# filter.net
KiCad netlist of a schematic drawn in Altium Designer
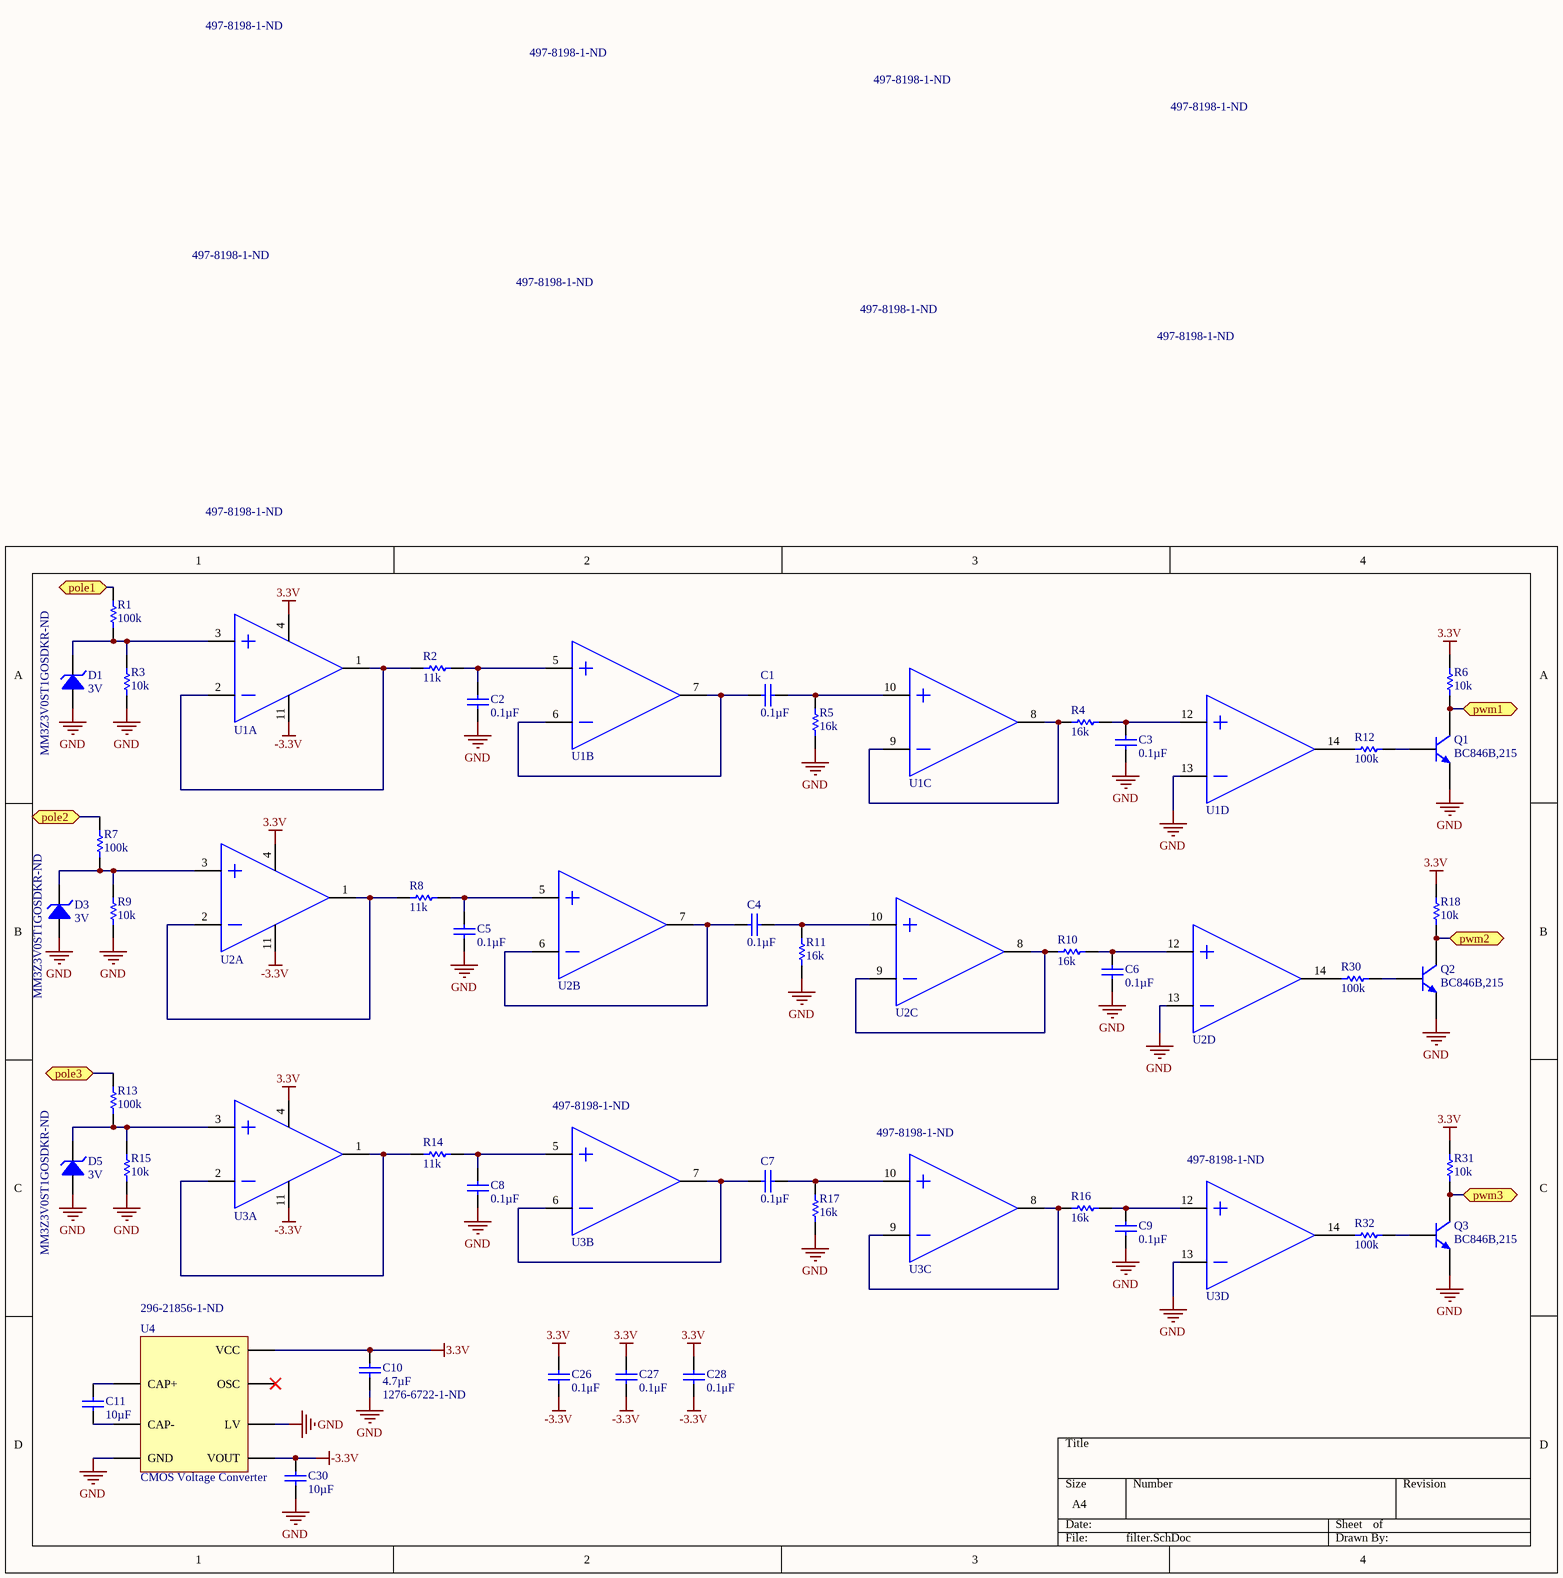
[diagram p0: filter.SchDoc]

(export (version "E")
  (design (tool "Eeschema 10.0.6"))
  (components
    (comp (ref "C1")
      (value "0.1uF, 50V, 10%, X7R, 1608")
      (footprint "CAPC1608N(0603\")")
      (description "CAP CER 0.1UF 50V 10% X7R 1608 (0603)")
      (fields
        (field (name "MANUFACTURER") "Samsung Electro-Mechanics America, Inc")
        (field (name "MANUFACTURER PART NUMBER") "CL10B104KB8SFNC")
        (field (name "CAPACITANCE") "0.1µF")
      )
      (libsource (lib "AUVic_Integrated_Library_Capacitors") (part "0.1uF, 50V, 10%, X7R, 1608"))
    )
    (comp (ref "C2")
      (value "0.1uF, 50V, 10%, X7R, 1608")
      (footprint "CAPC1608N(0603\")")
      (description "CAP CER 0.1UF 50V 10% X7R 1608 (0603)")
      (fields
        (field (name "MANUFACTURER") "Samsung Electro-Mechanics America, Inc")
        (field (name "MANUFACTURER PART NUMBER") "CL10B104KB8SFNC")
        (field (name "CAPACITANCE") "0.1µF")
      )
      (libsource (lib "AUVic_Integrated_Library_Capacitors") (part "0.1uF, 50V, 10%, X7R, 1608"))
    )
    (comp (ref "C3")
      (value "0.1uF, 50V, 10%, X7R, 1608")
      (footprint "CAPC1608N(0603\")")
      (description "CAP CER 0.1UF 50V 10% X7R 1608 (0603)")
      (fields
        (field (name "MANUFACTURER") "Samsung Electro-Mechanics America, Inc")
        (field (name "MANUFACTURER PART NUMBER") "CL10B104KB8SFNC")
        (field (name "CAPACITANCE") "0.1µF")
      )
      (libsource (lib "AUVic_Integrated_Library_Capacitors") (part "0.1uF, 50V, 10%, X7R, 1608"))
    )
    (comp (ref "C4")
      (value "0.1uF, 50V, 10%, X7R, 1608")
      (footprint "CAPC1608N(0603\")")
      (description "CAP CER 0.1UF 50V 10% X7R 1608 (0603)")
      (fields
        (field (name "MANUFACTURER") "Samsung Electro-Mechanics America, Inc")
        (field (name "MANUFACTURER PART NUMBER") "CL10B104KB8SFNC")
        (field (name "CAPACITANCE") "0.1µF")
      )
      (libsource (lib "AUVic_Integrated_Library_Capacitors") (part "0.1uF, 50V, 10%, X7R, 1608"))
    )
    (comp (ref "C5")
      (value "0.1uF, 50V, 10%, X7R, 1608")
      (footprint "CAPC1608N(0603\")")
      (description "CAP CER 0.1UF 50V 10% X7R 1608 (0603)")
      (fields
        (field (name "MANUFACTURER") "Samsung Electro-Mechanics America, Inc")
        (field (name "MANUFACTURER PART NUMBER") "CL10B104KB8SFNC")
        (field (name "CAPACITANCE") "0.1µF")
      )
      (libsource (lib "AUVic_Integrated_Library_Capacitors") (part "0.1uF, 50V, 10%, X7R, 1608"))
    )
    (comp (ref "C6")
      (value "0.1uF, 50V, 10%, X7R, 1608")
      (footprint "CAPC1608N(0603\")")
      (description "CAP CER 0.1UF 50V 10% X7R 1608 (0603)")
      (fields
        (field (name "MANUFACTURER") "Samsung Electro-Mechanics America, Inc")
        (field (name "MANUFACTURER PART NUMBER") "CL10B104KB8SFNC")
        (field (name "CAPACITANCE") "0.1µF")
      )
      (libsource (lib "AUVic_Integrated_Library_Capacitors") (part "0.1uF, 50V, 10%, X7R, 1608"))
    )
    (comp (ref "C7")
      (value "0.1uF, 50V, 10%, X7R, 1608")
      (footprint "CAPC1608N(0603\")")
      (description "CAP CER 0.1UF 50V 10% X7R 1608 (0603)")
      (fields
        (field (name "MANUFACTURER") "Samsung Electro-Mechanics America, Inc")
        (field (name "MANUFACTURER PART NUMBER") "CL10B104KB8SFNC")
        (field (name "CAPACITANCE") "0.1µF")
      )
      (libsource (lib "AUVic_Integrated_Library_Capacitors") (part "0.1uF, 50V, 10%, X7R, 1608"))
    )
    (comp (ref "C8")
      (value "0.1uF, 50V, 10%, X7R, 1608")
      (footprint "CAPC1608N(0603\")")
      (description "CAP CER 0.1UF 50V 10% X7R 1608 (0603)")
      (fields
        (field (name "MANUFACTURER") "Samsung Electro-Mechanics America, Inc")
        (field (name "MANUFACTURER PART NUMBER") "CL10B104KB8SFNC")
        (field (name "CAPACITANCE") "0.1µF")
      )
      (libsource (lib "AUVic_Integrated_Library_Capacitors") (part "0.1uF, 50V, 10%, X7R, 1608"))
    )
    (comp (ref "C9")
      (value "0.1uF, 50V, 10%, X7R, 1608")
      (footprint "CAPC1608N(0603\")")
      (description "CAP CER 0.1UF 50V 10% X7R 1608 (0603)")
      (fields
        (field (name "MANUFACTURER") "Samsung Electro-Mechanics America, Inc")
        (field (name "MANUFACTURER PART NUMBER") "CL10B104KB8SFNC")
        (field (name "CAPACITANCE") "0.1µF")
      )
      (libsource (lib "AUVic_Integrated_Library_Capacitors") (part "0.1uF, 50V, 10%, X7R, 1608"))
    )
    (comp (ref "C10")
      (value "4.7µF")
      (footprint "CAPC2012N(0805\")")
      (description "Capacitor, Ceramic, 35V, +/- 10%, 0805 SMD, X5R")
      (fields
        (field (name "SUPPLIER PART NUMBER 1") "1276-6722-1-ND")
        (field (name "PUBLISHER") "AUVic")
        (field (name "MADE BY") "Andy Bates")
      )
      (libsource (lib "AUVic_Integrated_Library_Capacitors") (part "4.7uF 35V 0805 SMD, Ceramic"))
    )
    (comp (ref "C11")
      (value "10µF")
      (footprint "CAPC3216N(1206\")")
      (description "Capacitor, Ceramic, 50V, +/- 10%, 1206 SMD, X5R")
      (fields (field (name "PUBLISHER") "AUVic"))
      (libsource (lib "AUVic_Integrated_Library_Capacitors") (part "10uF 50V 1206 SMD, Ceramic"))
    )
    (comp (ref "C26")
      (value "0.1μF")
      (footprint "CAPC1608N(0603\")")
      (description "Capacitor, Ceramic, 100V, +/- 10%, 0603 SMD, X7R")
      (fields
        (field (name "MFG") "TDK")
        (field (name "PUBLISHER") "AUVic")
        (field (name "CREATED BY") "Ashwin Sira")
      )
      (libsource (lib "AUVic_Integrated_Library_Capacitors") (part "0.1uF 100V 0603 SMD, Ceramic"))
    )
    (comp (ref "C27")
      (value "0.1μF")
      (footprint "CAPC1608N(0603\")")
      (description "Capacitor, Ceramic, 100V, +/- 10%, 0603 SMD, X7R")
      (fields
        (field (name "MFG") "TDK")
        (field (name "PUBLISHER") "AUVic")
        (field (name "CREATED BY") "Ashwin Sira")
      )
      (libsource (lib "AUVic_Integrated_Library_Capacitors") (part "0.1uF 100V 0603 SMD, Ceramic"))
    )
    (comp (ref "C28")
      (value "0.1μF")
      (footprint "CAPC1608N(0603\")")
      (description "Capacitor, Ceramic, 100V, +/- 10%, 0603 SMD, X7R")
      (fields
        (field (name "MFG") "TDK")
        (field (name "PUBLISHER") "AUVic")
        (field (name "CREATED BY") "Ashwin Sira")
      )
      (libsource (lib "AUVic_Integrated_Library_Capacitors") (part "0.1uF 100V 0603 SMD, Ceramic"))
    )
    (comp (ref "C30")
      (value "10µF")
      (footprint "CAPC2012N(0805\")")
      (description "Capacitor, Ceramic, 10V, +/- 10%, 0805 SMD, X5R")
      (fields (field (name "PUBLISHER") "AUVic") (field (name "MADE BY") "Andy Bates"))
      (libsource (lib "AUVic_Integrated_Library_Capacitors") (part "10uF 10V 0805 SMD, Ceramic"))
    )
    (comp (ref "D1")
      (value "ZENER MM3Z3V0ST1G")
      (footprint "SC-90")
      (description "DIODE ZENER 11V 200MW ±5% SOD323")
      (fields
        (field (name "TOLERANCE") "±5%")
        (field (name "VOLTAGE - ZENER (NOM) (VZ)") "3V")
        (field (name "SUPPLIER PART NUMBER 1") "MM3Z3V0ST1GOSDKR-ND")
      )
      (libsource (lib "AUVic_Integrated_Library_Diodes") (part "ZENER MM3Z3V0ST1G"))
    )
    (comp (ref "D3")
      (value "ZENER MM3Z3V0ST1G")
      (footprint "SC-90")
      (description "DIODE ZENER 11V 200MW ±5% SOD323")
      (fields
        (field (name "TOLERANCE") "±5%")
        (field (name "VOLTAGE - ZENER (NOM) (VZ)") "3V")
        (field (name "SUPPLIER PART NUMBER 1") "MM3Z3V0ST1GOSDKR-ND")
      )
      (libsource (lib "AUVic_Integrated_Library_Diodes") (part "ZENER MM3Z3V0ST1G"))
    )
    (comp (ref "D5")
      (value "ZENER MM3Z3V0ST1G")
      (footprint "SC-90")
      (description "DIODE ZENER 11V 200MW ±5% SOD323")
      (fields
        (field (name "TOLERANCE") "±5%")
        (field (name "VOLTAGE - ZENER (NOM) (VZ)") "3V")
        (field (name "SUPPLIER PART NUMBER 1") "MM3Z3V0ST1GOSDKR-ND")
      )
      (libsource (lib "AUVic_Integrated_Library_Diodes") (part "ZENER MM3Z3V0ST1G"))
    )
    (comp (ref "Q1")
      (value "BC846B,215")
      (footprint "SOT-23")
      (description "NPN 65V 100mA 250mW")
      (fields (field (name "PUBLISHER") "Andy Bates"))
      (libsource (lib "AUVic_Integrated_Library_Transistors") (part "BC846B,215"))
    )
    (comp (ref "Q2")
      (value "BC846B,215")
      (footprint "SOT-23")
      (description "NPN 65V 100mA 250mW")
      (fields (field (name "PUBLISHER") "Andy Bates"))
      (libsource (lib "AUVic_Integrated_Library_Transistors") (part "BC846B,215"))
    )
    (comp (ref "Q3")
      (value "BC846B,215")
      (footprint "SOT-23")
      (description "NPN 65V 100mA 250mW")
      (fields (field (name "PUBLISHER") "Andy Bates"))
      (libsource (lib "AUVic_Integrated_Library_Transistors") (part "BC846B,215"))
    )
    (comp (ref "R1")
      (value "100k")
      (footprint "RESC1608N(0603\")")
      (description "100kR, 1%, 1/10W, 0603 SMD")
      (fields (field (name "MADE BY") "Andy Bates"))
      (libsource (lib "AUVic_Integrated_Library_Resistors") (part "100kR, 1%, 1/10W, 0603 SMD"))
    )
    (comp (ref "R2")
      (value "11k")
      (footprint "RESC1608N(0603\")")
      (description "11kR, 1%, 1/10W, 0603 SMD")
      (fields (field (name "MADE BY") "Ashwin Sira"))
      (libsource (lib "AUVic_Integrated_Library_Resistors") (part "11kR, 1%, 1/10W, 0603 SMD"))
    )
    (comp (ref "R3")
      (value "10k")
      (footprint "RESC1608N(0603\")")
      (description "10kR, 1%, 1/10W, 0603 SMD")
      (fields (field (name "MADE BY") "Ashwin Sira"))
      (libsource (lib "AUVic_Integrated_Library_Resistors") (part "10kR, 1%, 1/10W, 0603 SMD"))
    )
    (comp (ref "R4")
      (value "16k")
      (footprint "RESC1608N(0603\")")
      (description "16kR, 1%, 1/10W, 0603 SMD")
      (fields (field (name "MADE BY") "Ashwin Sira"))
      (libsource (lib "AUVic_Integrated_Library_Resistors") (part "16kR, 1%, 1/10W, 0603 SMD"))
    )
    (comp (ref "R5")
      (value "16k")
      (footprint "RESC1608N(0603\")")
      (description "16kR, 1%, 1/10W, 0603 SMD")
      (fields (field (name "MADE BY") "Ashwin Sira"))
      (libsource (lib "AUVic_Integrated_Library_Resistors") (part "16kR, 1%, 1/10W, 0603 SMD"))
    )
    (comp (ref "R6")
      (value "10k")
      (footprint "RESC1608N(0603\")")
      (description "10kR, 1%, 1/10W, 0603 SMD")
      (fields (field (name "MADE BY") "Ashwin Sira"))
      (libsource (lib "AUVic_Integrated_Library_Resistors") (part "10kR, 1%, 1/10W, 0603 SMD"))
    )
    (comp (ref "R7")
      (value "100k")
      (footprint "RESC1608N(0603\")")
      (description "100kR, 1%, 1/10W, 0603 SMD")
      (fields (field (name "MADE BY") "Andy Bates"))
      (libsource (lib "AUVic_Integrated_Library_Resistors") (part "100kR, 1%, 1/10W, 0603 SMD"))
    )
    (comp (ref "R8")
      (value "11k")
      (footprint "RESC1608N(0603\")")
      (description "11kR, 1%, 1/10W, 0603 SMD")
      (fields (field (name "MADE BY") "Ashwin Sira"))
      (libsource (lib "AUVic_Integrated_Library_Resistors") (part "11kR, 1%, 1/10W, 0603 SMD"))
    )
    (comp (ref "R9")
      (value "10k")
      (footprint "RESC1608N(0603\")")
      (description "10kR, 1%, 1/10W, 0603 SMD")
      (fields (field (name "MADE BY") "Ashwin Sira"))
      (libsource (lib "AUVic_Integrated_Library_Resistors") (part "10kR, 1%, 1/10W, 0603 SMD"))
    )
    (comp (ref "R10")
      (value "16k")
      (footprint "RESC1608N(0603\")")
      (description "16kR, 1%, 1/10W, 0603 SMD")
      (fields (field (name "MADE BY") "Ashwin Sira"))
      (libsource (lib "AUVic_Integrated_Library_Resistors") (part "16kR, 1%, 1/10W, 0603 SMD"))
    )
    (comp (ref "R11")
      (value "16k")
      (footprint "RESC1608N(0603\")")
      (description "16kR, 1%, 1/10W, 0603 SMD")
      (fields (field (name "MADE BY") "Ashwin Sira"))
      (libsource (lib "AUVic_Integrated_Library_Resistors") (part "16kR, 1%, 1/10W, 0603 SMD"))
    )
    (comp (ref "R12")
      (value "100k")
      (footprint "RESC1608N(0603\")")
      (description "100kR, 1%, 1/10W, 0603 SMD")
      (fields (field (name "MADE BY") "Andy Bates"))
      (libsource (lib "AUVic_Integrated_Library_Resistors") (part "100kR, 1%, 1/10W, 0603 SMD"))
    )
    (comp (ref "R13")
      (value "100k")
      (footprint "RESC1608N(0603\")")
      (description "100kR, 1%, 1/10W, 0603 SMD")
      (fields (field (name "MADE BY") "Andy Bates"))
      (libsource (lib "AUVic_Integrated_Library_Resistors") (part "100kR, 1%, 1/10W, 0603 SMD"))
    )
    (comp (ref "R14")
      (value "11k")
      (footprint "RESC1608N(0603\")")
      (description "11kR, 1%, 1/10W, 0603 SMD")
      (fields (field (name "MADE BY") "Ashwin Sira"))
      (libsource (lib "AUVic_Integrated_Library_Resistors") (part "11kR, 1%, 1/10W, 0603 SMD"))
    )
    (comp (ref "R15")
      (value "10k")
      (footprint "RESC1608N(0603\")")
      (description "10kR, 1%, 1/10W, 0603 SMD")
      (fields (field (name "MADE BY") "Ashwin Sira"))
      (libsource (lib "AUVic_Integrated_Library_Resistors") (part "10kR, 1%, 1/10W, 0603 SMD"))
    )
    (comp (ref "R16")
      (value "16k")
      (footprint "RESC1608N(0603\")")
      (description "16kR, 1%, 1/10W, 0603 SMD")
      (fields (field (name "MADE BY") "Ashwin Sira"))
      (libsource (lib "AUVic_Integrated_Library_Resistors") (part "16kR, 1%, 1/10W, 0603 SMD"))
    )
    (comp (ref "R17")
      (value "16k")
      (footprint "RESC1608N(0603\")")
      (description "16kR, 1%, 1/10W, 0603 SMD")
      (fields (field (name "MADE BY") "Ashwin Sira"))
      (libsource (lib "AUVic_Integrated_Library_Resistors") (part "16kR, 1%, 1/10W, 0603 SMD"))
    )
    (comp (ref "R18")
      (value "10k")
      (footprint "RESC1608N(0603\")")
      (description "10kR, 1%, 1/10W, 0603 SMD")
      (fields (field (name "MADE BY") "Ashwin Sira"))
      (libsource (lib "AUVic_Integrated_Library_Resistors") (part "10kR, 1%, 1/10W, 0603 SMD"))
    )
    (comp (ref "R30")
      (value "100k")
      (footprint "RESC1608N(0603\")")
      (description "100kR, 1%, 1/10W, 0603 SMD")
      (fields (field (name "MADE BY") "Andy Bates"))
      (libsource (lib "AUVic_Integrated_Library_Resistors") (part "100kR, 1%, 1/10W, 0603 SMD"))
    )
    (comp (ref "R31")
      (value "10k")
      (footprint "RESC1608N(0603\")")
      (description "10kR, 1%, 1/10W, 0603 SMD")
      (fields (field (name "MADE BY") "Ashwin Sira"))
      (libsource (lib "AUVic_Integrated_Library_Resistors") (part "10kR, 1%, 1/10W, 0603 SMD"))
    )
    (comp (ref "R32")
      (value "100k")
      (footprint "RESC1608N(0603\")")
      (description "100kR, 1%, 1/10W, 0603 SMD")
      (fields (field (name "MADE BY") "Andy Bates"))
      (libsource (lib "AUVic_Integrated_Library_Resistors") (part "100kR, 1%, 1/10W, 0603 SMD"))
    )
    (comp (ref "U1")
      (value "Quad Op Amp TSV324")
      (footprint "SOP-14")
      (description "TSV324")
      (fields
        (field (name "SUPPLIER PART NUMBER 1") "497-8198-1-ND")
        (field (name "PUBLISHER") "Altium Limited")
        (field (name "CREATED BY") "Jordan")
      )
      (libsource (lib "AUVic_Integrated_Library_Op_amps") (part "Quad Op Amp TSV324"))
    )
    (comp (ref "U2")
      (value "Quad Op Amp TSV324")
      (footprint "SOP-14")
      (description "TSV324")
      (fields
        (field (name "SUPPLIER PART NUMBER 1") "497-8198-1-ND")
        (field (name "PUBLISHER") "Altium Limited")
        (field (name "CREATED BY") "Jordan")
      )
      (libsource (lib "AUVic_Integrated_Library_Op_amps") (part "Quad Op Amp TSV324"))
    )
    (comp (ref "U3")
      (value "Quad Op Amp TSV324")
      (footprint "SOP-14")
      (description "TSV324")
      (fields
        (field (name "SUPPLIER PART NUMBER 1") "497-8198-1-ND")
        (field (name "PUBLISHER") "Altium Limited")
        (field (name "CREATED BY") "Jordan")
      )
      (libsource (lib "AUVic_Integrated_Library_Op_amps") (part "Quad Op Amp TSV324"))
    )
    (comp (ref "U4")
      (value "CMOS Voltage Converter")
      (footprint "8-SOIC")
      (fields
        (field (name "MANUFACTURER PART NO.") "TL7660")
        (field (name "SUPPLIER PART NUMBER 1") "296-21856-1-ND")
        (field (name "PUBLISHER") "Altium Limited")
        (field (name "CREATED BY") "Jordan")
      )
      (libsource (lib "AUVic_Integrated_Library_Regulators") (part "TL7660"))
    )
  )
  (nets
    (net (code "1") (name "-3.3V") (class "Default")
      (node (ref "C26") (pin "1") (pinfunction "Anode_1") (pintype "passive"))
      (node (ref "C27") (pin "1") (pinfunction "Anode_1") (pintype "passive"))
      (node (ref "C28") (pin "1") (pinfunction "Anode_1") (pintype "passive"))
      (node (ref "C30") (pin "2") (pinfunction "Cathode_2") (pintype "passive"))
      (node (ref "U1") (pin "11") (pinfunction "Vcc-_11") (pintype "passive"))
      (node (ref "U2") (pin "11") (pinfunction "Vcc-_11") (pintype "passive"))
      (node (ref "U3") (pin "11") (pinfunction "Vcc-_11") (pintype "passive"))
      (node (ref "U4") (pin "5") (pinfunction "VOUT_5") (pintype "passive"))
    )
    (net (code "2") (name "/pole1") (class "Default")
      (node (ref "R1") (pin "2") (pinfunction "2_2") (pintype "passive"))
    )
    (net (code "3") (name "/pole2") (class "Default")
      (node (ref "R7") (pin "2") (pinfunction "2_2") (pintype "passive"))
    )
    (net (code "4") (name "/pole3") (class "Default")
      (node (ref "R13") (pin "2") (pinfunction "2_2") (pintype "passive"))
    )
    (net (code "5") (name "/pwm1") (class "Default")
      (node (ref "Q1") (pin "3") (pinfunction "C_3") (pintype "passive"))
      (node (ref "R6") (pin "1") (pinfunction "1_1") (pintype "passive"))
    )
    (net (code "6") (name "/pwm2") (class "Default")
      (node (ref "Q2") (pin "3") (pinfunction "C_3") (pintype "passive"))
      (node (ref "R18") (pin "1") (pinfunction "1_1") (pintype "passive"))
    )
    (net (code "7") (name "/pwm3") (class "Default")
      (node (ref "Q3") (pin "3") (pinfunction "C_3") (pintype "passive"))
      (node (ref "R31") (pin "1") (pinfunction "1_1") (pintype "passive"))
    )
    (net (code "8") (name "3.3V") (class "Default")
      (node (ref "C10") (pin "2") (pinfunction "Cathode_2") (pintype "passive"))
      (node (ref "C26") (pin "2") (pinfunction "Cathode_2") (pintype "passive"))
      (node (ref "C27") (pin "2") (pinfunction "Cathode_2") (pintype "passive"))
      (node (ref "C28") (pin "2") (pinfunction "Cathode_2") (pintype "passive"))
      (node (ref "R18") (pin "2") (pinfunction "2_2") (pintype "passive"))
      (node (ref "R31") (pin "2") (pinfunction "2_2") (pintype "passive"))
      (node (ref "R6") (pin "2") (pinfunction "2_2") (pintype "passive"))
      (node (ref "U1") (pin "4") (pinfunction "Vcc+_4") (pintype "passive"))
      (node (ref "U2") (pin "4") (pinfunction "Vcc+_4") (pintype "passive"))
      (node (ref "U3") (pin "4") (pinfunction "Vcc+_4") (pintype "passive"))
      (node (ref "U4") (pin "8") (pinfunction "VCC_8") (pintype "passive"))
    )
    (net (code "9") (name "GND") (class "Default")
      (node (ref "C10") (pin "1") (pinfunction "Anode_1") (pintype "passive"))
      (node (ref "C2") (pin "1") (pinfunction "Anode_1") (pintype "passive"))
      (node (ref "C3") (pin "1") (pinfunction "Anode_1") (pintype "passive"))
      (node (ref "C30") (pin "1") (pinfunction "Anode_1") (pintype "passive"))
      (node (ref "C5") (pin "1") (pinfunction "Anode_1") (pintype "passive"))
      (node (ref "C6") (pin "1") (pinfunction "Anode_1") (pintype "passive"))
      (node (ref "C8") (pin "1") (pinfunction "Anode_1") (pintype "passive"))
      (node (ref "C9") (pin "1") (pinfunction "Anode_1") (pintype "passive"))
      (node (ref "D1") (pin "A") (pinfunction "Anode_A") (pintype "passive"))
      (node (ref "D3") (pin "A") (pinfunction "Anode_A") (pintype "passive"))
      (node (ref "D5") (pin "A") (pinfunction "Anode_A") (pintype "passive"))
      (node (ref "Q1") (pin "2") (pinfunction "E_2") (pintype "passive"))
      (node (ref "Q2") (pin "2") (pinfunction "E_2") (pintype "passive"))
      (node (ref "Q3") (pin "2") (pinfunction "E_2") (pintype "passive"))
      (node (ref "R11") (pin "1") (pinfunction "1_1") (pintype "passive"))
      (node (ref "R15") (pin "1") (pinfunction "1_1") (pintype "passive"))
      (node (ref "R17") (pin "1") (pinfunction "1_1") (pintype "passive"))
      (node (ref "R3") (pin "1") (pinfunction "1_1") (pintype "passive"))
      (node (ref "R5") (pin "1") (pinfunction "1_1") (pintype "passive"))
      (node (ref "R9") (pin "1") (pinfunction "1_1") (pintype "passive"))
      (node (ref "U1") (pin "13") (pinfunction "Inverting_Input_3_13") (pintype "passive"))
      (node (ref "U2") (pin "13") (pinfunction "Inverting_Input_3_13") (pintype "passive"))
      (node (ref "U3") (pin "13") (pinfunction "Inverting_Input_3_13") (pintype "passive"))
      (node (ref "U4") (pin "3") (pinfunction "GND_3") (pintype "passive"))
      (node (ref "U4") (pin "6") (pinfunction "LV_6") (pintype "passive"))
    )
    (net (code "10") (name "Net-(C1-Anode)") (class "Default")
      (node (ref "C1") (pin "1") (pinfunction "Anode_1") (pintype "passive"))
      (node (ref "U1") (pin "6") (pinfunction "Inverting_Input_2_6") (pintype "passive"))
      (node (ref "U1") (pin "7") (pinfunction "Output_2_7") (pintype "passive"))
    )
    (net (code "11") (name "Net-(C1-Cathode)") (class "Default")
      (node (ref "C1") (pin "2") (pinfunction "Cathode_2") (pintype "passive"))
      (node (ref "R5") (pin "2") (pinfunction "2_2") (pintype "passive"))
      (node (ref "U1") (pin "10") (pinfunction "Non-Inverting_Input_3_10") (pintype "passive"))
    )
    (net (code "12") (name "Net-(C2-Cathode)") (class "Default")
      (node (ref "C2") (pin "2") (pinfunction "Cathode_2") (pintype "passive"))
      (node (ref "R2") (pin "2") (pinfunction "2_2") (pintype "passive"))
      (node (ref "U1") (pin "5") (pinfunction "Non-Inverting_Input_2_5") (pintype "passive"))
    )
    (net (code "13") (name "Net-(C3-Cathode)") (class "Default")
      (node (ref "C3") (pin "2") (pinfunction "Cathode_2") (pintype "passive"))
      (node (ref "R4") (pin "1") (pinfunction "1_1") (pintype "passive"))
      (node (ref "U1") (pin "12") (pinfunction "Non-Inverting_Input_4_12") (pintype "passive"))
    )
    (net (code "14") (name "Net-(C4-Anode)") (class "Default")
      (node (ref "C4") (pin "1") (pinfunction "Anode_1") (pintype "passive"))
      (node (ref "U2") (pin "6") (pinfunction "Inverting_Input_2_6") (pintype "passive"))
      (node (ref "U2") (pin "7") (pinfunction "Output_2_7") (pintype "passive"))
    )
    (net (code "15") (name "Net-(C4-Cathode)") (class "Default")
      (node (ref "C4") (pin "2") (pinfunction "Cathode_2") (pintype "passive"))
      (node (ref "R11") (pin "2") (pinfunction "2_2") (pintype "passive"))
      (node (ref "U2") (pin "10") (pinfunction "Non-Inverting_Input_3_10") (pintype "passive"))
    )
    (net (code "16") (name "Net-(C5-Cathode)") (class "Default")
      (node (ref "C5") (pin "2") (pinfunction "Cathode_2") (pintype "passive"))
      (node (ref "R8") (pin "2") (pinfunction "2_2") (pintype "passive"))
      (node (ref "U2") (pin "5") (pinfunction "Non-Inverting_Input_2_5") (pintype "passive"))
    )
    (net (code "17") (name "Net-(C6-Cathode)") (class "Default")
      (node (ref "C6") (pin "2") (pinfunction "Cathode_2") (pintype "passive"))
      (node (ref "R10") (pin "1") (pinfunction "1_1") (pintype "passive"))
      (node (ref "U2") (pin "12") (pinfunction "Non-Inverting_Input_4_12") (pintype "passive"))
    )
    (net (code "18") (name "Net-(C7-Anode)") (class "Default")
      (node (ref "C7") (pin "1") (pinfunction "Anode_1") (pintype "passive"))
      (node (ref "U3") (pin "6") (pinfunction "Inverting_Input_2_6") (pintype "passive"))
      (node (ref "U3") (pin "7") (pinfunction "Output_2_7") (pintype "passive"))
    )
    (net (code "19") (name "Net-(C7-Cathode)") (class "Default")
      (node (ref "C7") (pin "2") (pinfunction "Cathode_2") (pintype "passive"))
      (node (ref "R17") (pin "2") (pinfunction "2_2") (pintype "passive"))
      (node (ref "U3") (pin "10") (pinfunction "Non-Inverting_Input_3_10") (pintype "passive"))
    )
    (net (code "20") (name "Net-(C8-Cathode)") (class "Default")
      (node (ref "C8") (pin "2") (pinfunction "Cathode_2") (pintype "passive"))
      (node (ref "R14") (pin "2") (pinfunction "2_2") (pintype "passive"))
      (node (ref "U3") (pin "5") (pinfunction "Non-Inverting_Input_2_5") (pintype "passive"))
    )
    (net (code "21") (name "Net-(C9-Cathode)") (class "Default")
      (node (ref "C9") (pin "2") (pinfunction "Cathode_2") (pintype "passive"))
      (node (ref "R16") (pin "1") (pinfunction "1_1") (pintype "passive"))
      (node (ref "U3") (pin "12") (pinfunction "Non-Inverting_Input_4_12") (pintype "passive"))
    )
    (net (code "22") (name "Net-(C11-Anode)") (class "Default")
      (node (ref "C11") (pin "1") (pinfunction "Anode_1") (pintype "passive"))
      (node (ref "U4") (pin "4") (pinfunction "CAP-_4") (pintype "passive"))
    )
    (net (code "23") (name "Net-(C11-Cathode)") (class "Default")
      (node (ref "C11") (pin "2") (pinfunction "Cathode_2") (pintype "passive"))
      (node (ref "U4") (pin "2") (pinfunction "CAP+_2") (pintype "passive"))
    )
    (net (code "24") (name "Net-(D1-Cathode)") (class "Default")
      (node (ref "D1") (pin "K") (pinfunction "Cathode_K") (pintype "passive"))
      (node (ref "R1") (pin "1") (pinfunction "1_1") (pintype "passive"))
      (node (ref "R3") (pin "2") (pinfunction "2_2") (pintype "passive"))
      (node (ref "U1") (pin "3") (pinfunction "Non-Inverting_Input_1_3") (pintype "passive"))
    )
    (net (code "25") (name "Net-(D3-Cathode)") (class "Default")
      (node (ref "D3") (pin "K") (pinfunction "Cathode_K") (pintype "passive"))
      (node (ref "R7") (pin "1") (pinfunction "1_1") (pintype "passive"))
      (node (ref "R9") (pin "2") (pinfunction "2_2") (pintype "passive"))
      (node (ref "U2") (pin "3") (pinfunction "Non-Inverting_Input_1_3") (pintype "passive"))
    )
    (net (code "26") (name "Net-(D5-Cathode)") (class "Default")
      (node (ref "D5") (pin "K") (pinfunction "Cathode_K") (pintype "passive"))
      (node (ref "R13") (pin "1") (pinfunction "1_1") (pintype "passive"))
      (node (ref "R15") (pin "2") (pinfunction "2_2") (pintype "passive"))
      (node (ref "U3") (pin "3") (pinfunction "Non-Inverting_Input_1_3") (pintype "passive"))
    )
    (net (code "27") (name "Net-(Q1-B)") (class "Default")
      (node (ref "Q1") (pin "1") (pinfunction "B_1") (pintype "passive"))
      (node (ref "R12") (pin "2") (pinfunction "2_2") (pintype "passive"))
    )
    (net (code "28") (name "Net-(Q2-B)") (class "Default")
      (node (ref "Q2") (pin "1") (pinfunction "B_1") (pintype "passive"))
      (node (ref "R30") (pin "2") (pinfunction "2_2") (pintype "passive"))
    )
    (net (code "29") (name "Net-(Q3-B)") (class "Default")
      (node (ref "Q3") (pin "1") (pinfunction "B_1") (pintype "passive"))
      (node (ref "R32") (pin "2") (pinfunction "2_2") (pintype "passive"))
    )
    (net (code "30") (name "Net-(U1A-Inverting_Input_1)") (class "Default")
      (node (ref "R2") (pin "1") (pinfunction "1_1") (pintype "passive"))
      (node (ref "U1") (pin "1") (pinfunction "Output_1_1") (pintype "passive"))
      (node (ref "U1") (pin "2") (pinfunction "Inverting_Input_1_2") (pintype "passive"))
    )
    (net (code "31") (name "Net-(U1C-Inverting_Input_3)") (class "Default")
      (node (ref "R4") (pin "2") (pinfunction "2_2") (pintype "passive"))
      (node (ref "U1") (pin "8") (pinfunction "Output_3_8") (pintype "passive"))
      (node (ref "U1") (pin "9") (pinfunction "Inverting_Input_3_9") (pintype "passive"))
    )
    (net (code "32") (name "Net-(U1D-Output_4)") (class "Default")
      (node (ref "R12") (pin "1") (pinfunction "1_1") (pintype "passive"))
      (node (ref "U1") (pin "14") (pinfunction "Output_4_14") (pintype "passive"))
    )
    (net (code "33") (name "Net-(U2A-Inverting_Input_1)") (class "Default")
      (node (ref "R8") (pin "1") (pinfunction "1_1") (pintype "passive"))
      (node (ref "U2") (pin "1") (pinfunction "Output_1_1") (pintype "passive"))
      (node (ref "U2") (pin "2") (pinfunction "Inverting_Input_1_2") (pintype "passive"))
    )
    (net (code "34") (name "Net-(U2C-Inverting_Input_3)") (class "Default")
      (node (ref "R10") (pin "2") (pinfunction "2_2") (pintype "passive"))
      (node (ref "U2") (pin "8") (pinfunction "Output_3_8") (pintype "passive"))
      (node (ref "U2") (pin "9") (pinfunction "Inverting_Input_3_9") (pintype "passive"))
    )
    (net (code "35") (name "Net-(U2D-Output_4)") (class "Default")
      (node (ref "R30") (pin "1") (pinfunction "1_1") (pintype "passive"))
      (node (ref "U2") (pin "14") (pinfunction "Output_4_14") (pintype "passive"))
    )
    (net (code "36") (name "Net-(U3A-Inverting_Input_1)") (class "Default")
      (node (ref "R14") (pin "1") (pinfunction "1_1") (pintype "passive"))
      (node (ref "U3") (pin "1") (pinfunction "Output_1_1") (pintype "passive"))
      (node (ref "U3") (pin "2") (pinfunction "Inverting_Input_1_2") (pintype "passive"))
    )
    (net (code "37") (name "Net-(U3C-Inverting_Input_3)") (class "Default")
      (node (ref "R16") (pin "2") (pinfunction "2_2") (pintype "passive"))
      (node (ref "U3") (pin "8") (pinfunction "Output_3_8") (pintype "passive"))
      (node (ref "U3") (pin "9") (pinfunction "Inverting_Input_3_9") (pintype "passive"))
    )
    (net (code "38") (name "Net-(U3D-Output_4)") (class "Default")
      (node (ref "R32") (pin "1") (pinfunction "1_1") (pintype "passive"))
      (node (ref "U3") (pin "14") (pinfunction "Output_4_14") (pintype "passive"))
    )
    (net (code "39") (name "unconnected-(U4-OSC-Pad7)") (class "Default")
      (node (ref "U4") (pin "7") (pinfunction "OSC_7") (pintype "passive+no_connect"))
    )
  )
)
